# DRV8301.net
KiCad netlist of a schematic drawn in Altium Designer
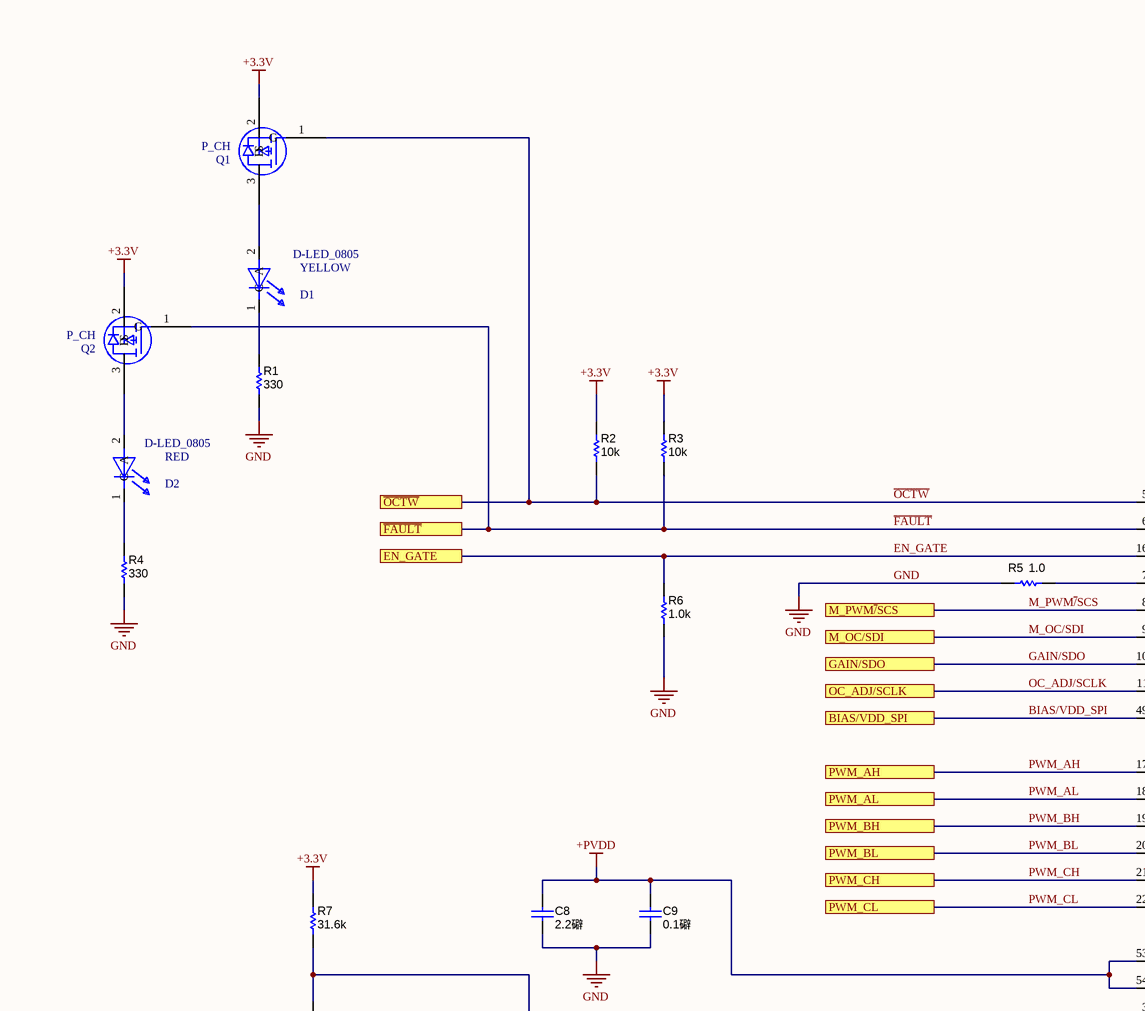
[diagram p0: DRV8301.SchDoc, top left]
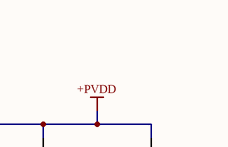
[diagram p1: DRV8301.SchDoc, top right]
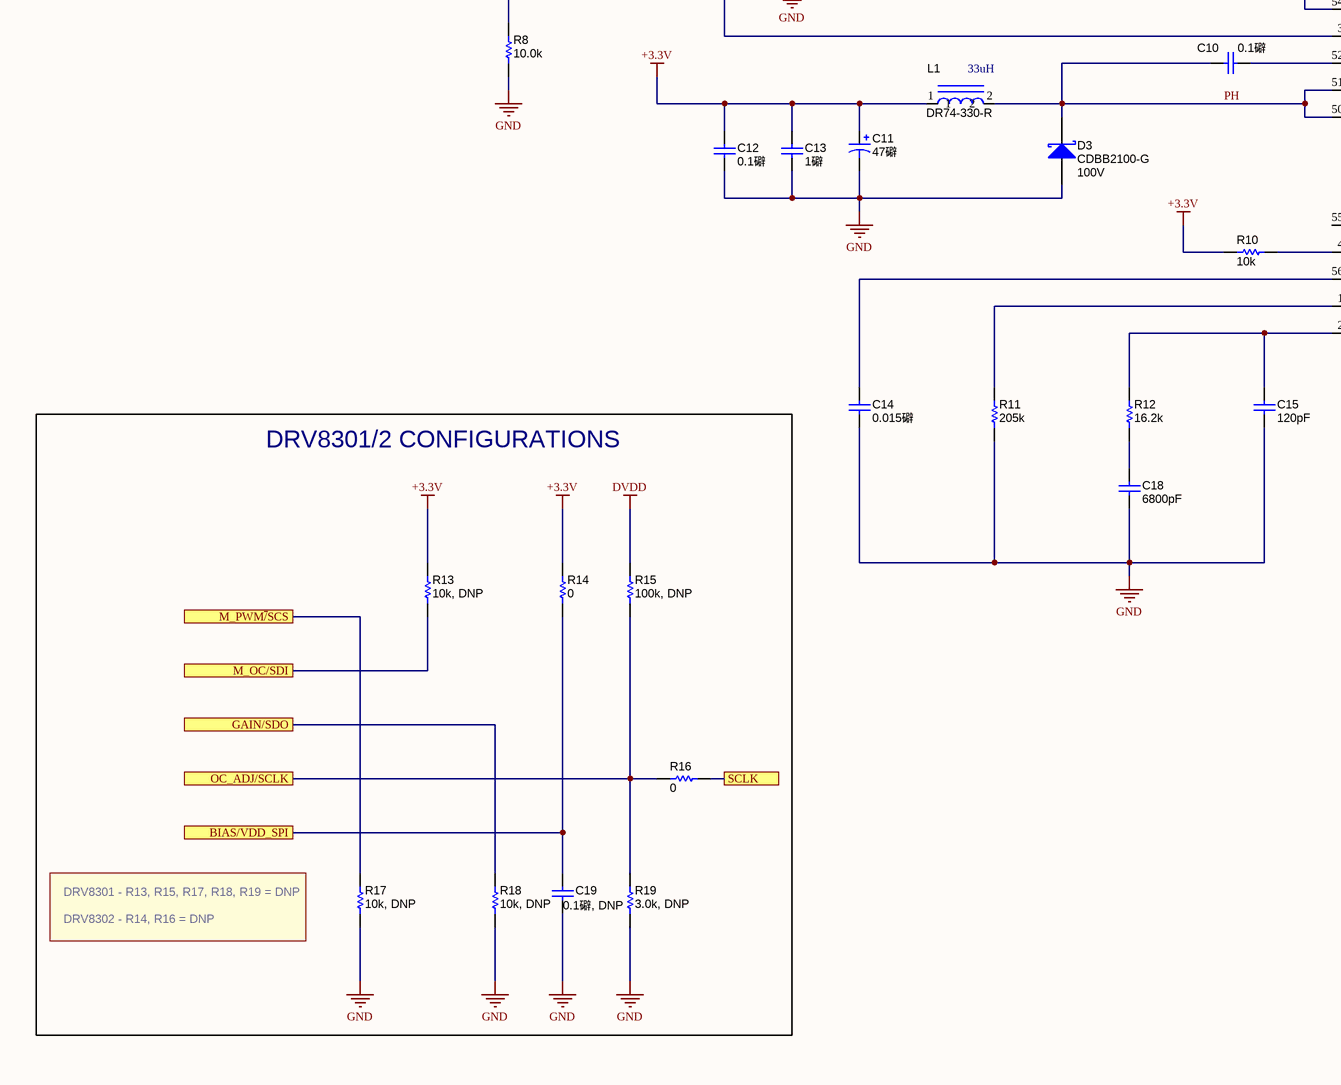
[diagram p2: DRV8301.SchDoc, bottom left]
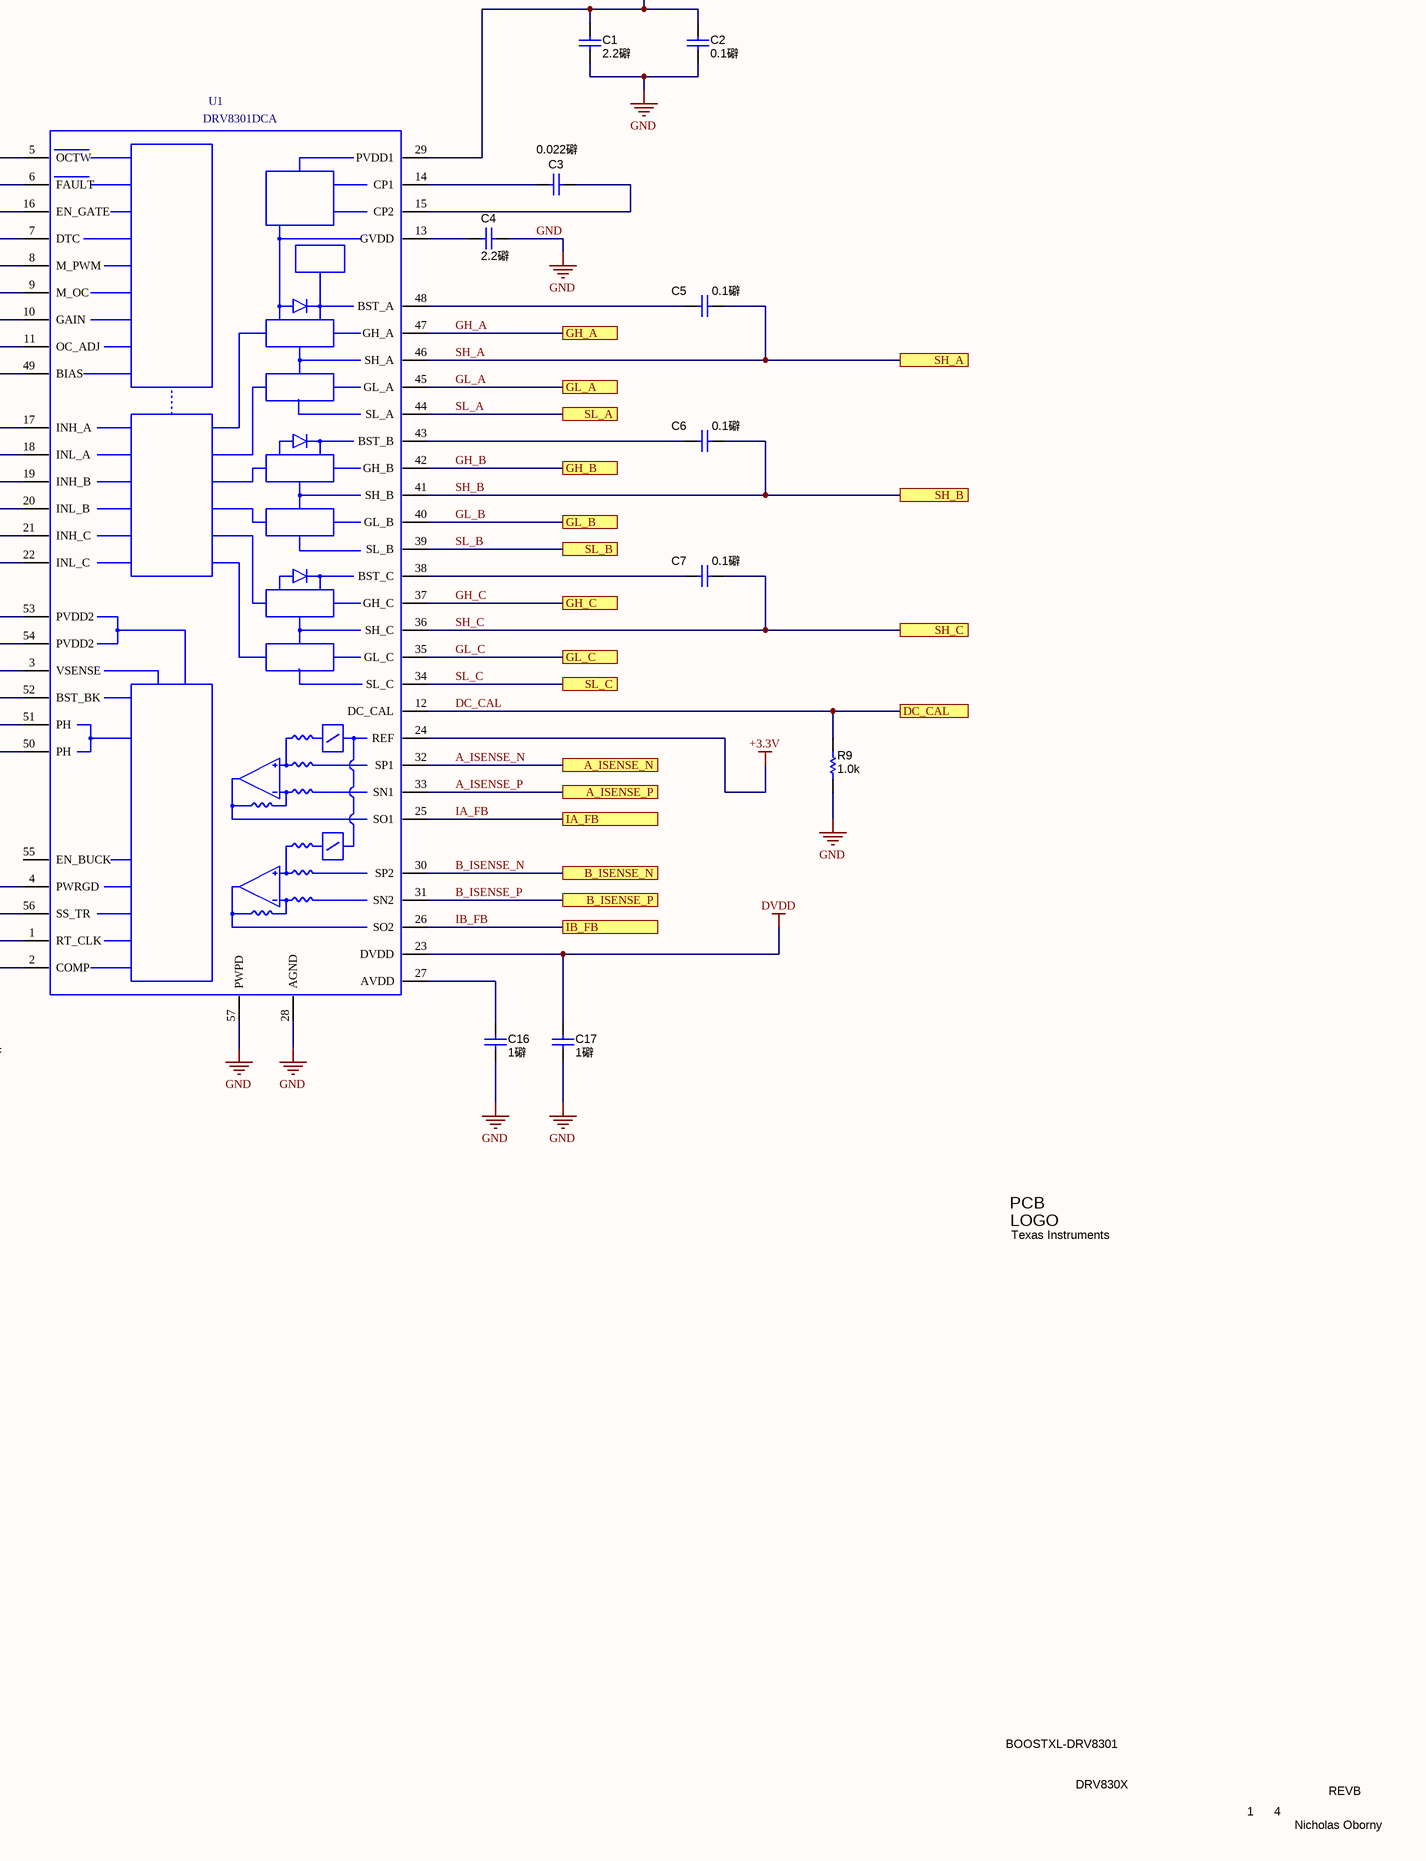
[diagram p3: DRV8301.SchDoc, bottom right]

(export (version "E")
  (design (tool "Eeschema 10.0.6"))
  (components
    (comp (ref "C1")
      (value "GRM32ER72A225KA35L")
      (footprint "1210L")
      (description "CAP, CERM, 2.2uF, 100V, +/-10%, X7R, 1210")
      (fields
        (field (name "VALUEDISPLAYED") "2.2礔")
        (field (name "MANUFACTURER") "MuRata")
        (field (name "PUBLISHER") "Texas Instruments")
      )
      (libsource (lib "Capacitor_Ceramic") (part "GRM32ER72A225KA35L"))
    )
    (comp (ref "C2")
      (value "GRM188R72A104KA35D")
      (footprint "0603L")
      (description "CAP, CERM, 0.1uF, 100V, +/-10%, X7R, 0603")
      (fields
        (field (name "VALUEDISPLAYED") "0.1礔")
        (field (name "MANUFACTURER") "MuRata")
        (field (name "PUBLISHER") "Texas Instruments")
      )
      (libsource (lib "Capacitor_Ceramic") (part "GRM188R72A104KA35D"))
    )
    (comp (ref "C3")
      (value "C1608X7R1H223K")
      (footprint "0603L")
      (description "CAP, CERM, 0.022uF, 50V, +/-10%, X7R, 0603")
      (fields
        (field (name "VALUEDISPLAYED") "0.022礔")
        (field (name "MANUFACTURER") "TDK")
        (field (name "PUBLISHER") "Texas Instruments")
      )
      (libsource (lib "Capacitor_Ceramic") (part "C1608X7R1H223K"))
    )
    (comp (ref "C4")
      (value "GRM219R61E225KA12D")
      (footprint "0805L")
      (description "CAP, CERM, 2.2uF, 25V, +/-10%, X5R, 0805")
      (fields
        (field (name "VALUEDISPLAYED") "2.2礔")
        (field (name "MANUFACTURER") "MuRata")
        (field (name "PUBLISHER") "Texas Instruments")
      )
      (libsource (lib "Capacitor_Ceramic") (part "GRM219R61E225KA12D"))
    )
    (comp (ref "C5")
      (value "C1608X7R1H104K")
      (footprint "0603L")
      (description "CAP, CERM, 0.1uF, 50V, +/-10%, X7R, 0603")
      (fields
        (field (name "VALUEDISPLAYED") "0.1礔")
        (field (name "MANUFACTURER") "TDK")
        (field (name "PUBLISHER") "Texas Instruments")
      )
      (libsource (lib "Capacitor_Ceramic") (part "C1608X7R1H104K"))
    )
    (comp (ref "C6")
      (value "C1608X7R1H104K")
      (footprint "0603L")
      (description "CAP, CERM, 0.1uF, 50V, +/-10%, X7R, 0603")
      (fields
        (field (name "VALUEDISPLAYED") "0.1礔")
        (field (name "MANUFACTURER") "TDK")
        (field (name "PUBLISHER") "Texas Instruments")
      )
      (libsource (lib "Capacitor_Ceramic") (part "C1608X7R1H104K"))
    )
    (comp (ref "C7")
      (value "C1608X7R1H104K")
      (footprint "0603L")
      (description "CAP, CERM, 0.1uF, 50V, +/-10%, X7R, 0603")
      (fields
        (field (name "VALUEDISPLAYED") "0.1礔")
        (field (name "MANUFACTURER") "TDK")
        (field (name "PUBLISHER") "Texas Instruments")
      )
      (libsource (lib "Capacitor_Ceramic") (part "C1608X7R1H104K"))
    )
    (comp (ref "C8")
      (value "GRM32ER72A225KA35L")
      (footprint "1210L")
      (description "CAP, CERM, 2.2uF, 100V, +/-10%, X7R, 1210")
      (fields
        (field (name "VALUEDISPLAYED") "2.2礔")
        (field (name "MANUFACTURER") "MuRata")
        (field (name "PUBLISHER") "Texas Instruments")
      )
      (libsource (lib "Capacitor_Ceramic") (part "GRM32ER72A225KA35L"))
    )
    (comp (ref "C9")
      (value "GRM188R72A104KA35D")
      (footprint "0603L")
      (description "CAP, CERM, 0.1uF, 100V, +/-10%, X7R, 0603")
      (fields
        (field (name "VALUEDISPLAYED") "0.1礔")
        (field (name "MANUFACTURER") "MuRata")
        (field (name "PUBLISHER") "Texas Instruments")
      )
      (libsource (lib "Capacitor_Ceramic") (part "GRM188R72A104KA35D"))
    )
    (comp (ref "C10")
      (value "C1608X7R1H104K")
      (footprint "0603L")
      (description "CAP, CERM, 0.1uF, 50V, +/-10%, X7R, 0603")
      (fields
        (field (name "VALUEDISPLAYED") "0.1礔")
        (field (name "MANUFACTURER") "TDK")
        (field (name "PUBLISHER") "Texas Instruments")
      )
      (libsource (lib "Capacitor_Ceramic") (part "C1608X7R1H104K"))
    )
    (comp (ref "C11")
      (value "EEE-FK1E470P")
      (footprint "SM_RADIAL_D")
      (description "CAP, AL, 47uF, 25V, +/-20%, 0.36 ohm, SMD")
      (fields
        (field (name "VALUEDISPLAYED") "47礔")
        (field (name "MANUFACTURER") "Panasonic")
        (field (name "PUBLISHER") "Texas Instruments")
      )
      (libsource (lib "Capacitor_Aluminum") (part "EEE-FK1E470P"))
    )
    (comp (ref "C12")
      (value "C1608X7R1E104K")
      (footprint "0603L")
      (description "CAP, CERM, 0.1uF, 25V, +/-10%, X7R, 0603")
      (fields
        (field (name "VALUEDISPLAYED") "0.1礔")
        (field (name "MANUFACTURER") "TDK")
        (field (name "PUBLISHER") "Texas Instruments")
      )
      (libsource (lib "Capacitor_Ceramic") (part "C1608X7R1E104K"))
    )
    (comp (ref "C13")
      (value "C1608X5R1E105K080AC")
      (footprint "0603L")
      (description "CAP, CERM, 1uF, 25V, +/-10%, X5R, 0603")
      (fields
        (field (name "VALUEDISPLAYED") "1礔")
        (field (name "MANUFACTURER") "TDK")
        (field (name "PUBLISHER") "Texas Instruments")
      )
      (libsource (lib "Capacitor_Ceramic") (part "C1608X5R1E105K080AC"))
    )
    (comp (ref "C14")
      (value "GRM188R71H153KA01D")
      (footprint "0603L")
      (description "CAP, CERM, 0.015uF, 50V, +/-10%, X7R, 0603")
      (fields
        (field (name "VALUEDISPLAYED") "0.015礔")
        (field (name "MANUFACTURER") "MuRata")
        (field (name "PUBLISHER") "Texas Instruments")
      )
      (libsource (lib "Capacitor_Ceramic") (part "GRM188R71H153KA01D"))
    )
    (comp (ref "C15")
      (value "GRM1885C1H121JA01D")
      (footprint "0603L")
      (description "CAP, CERM, 120pF, 50V, +/-5%, C0G/NP0, 0603")
      (fields
        (field (name "VALUEDISPLAYED") "120pF")
        (field (name "MANUFACTURER") "MuRata")
        (field (name "PUBLISHER") "Texas Instruments")
      )
      (libsource (lib "Capacitor_Ceramic") (part "GRM1885C1H121JA01D"))
    )
    (comp (ref "C16")
      (value "GRM188R61E105KA12D")
      (footprint "0603L")
      (description "CAP, CERM, 1uF, 25V, +/-10%, X5R, 0603")
      (fields
        (field (name "VALUEDISPLAYED") "1礔")
        (field (name "MANUFACTURER") "MuRata")
        (field (name "PUBLISHER") "Texas Instruments")
      )
      (libsource (lib "Capacitor_Ceramic") (part "GRM188R61E105KA12D"))
    )
    (comp (ref "C17")
      (value "GRM188R61E105KA12D")
      (footprint "0603L")
      (description "CAP, CERM, 1uF, 25V, +/-10%, X5R, 0603")
      (fields
        (field (name "VALUEDISPLAYED") "1礔")
        (field (name "MANUFACTURER") "MuRata")
        (field (name "PUBLISHER") "Texas Instruments")
      )
      (libsource (lib "Capacitor_Ceramic") (part "GRM188R61E105KA12D"))
    )
    (comp (ref "C18")
      (value "GRM188R71H682KA01D")
      (footprint "0603L")
      (description "CAP, CERM, 6800pF, 50V, +/-10%, X7R, 0603")
      (fields
        (field (name "VALUEDISPLAYED") "6800pF")
        (field (name "MANUFACTURER") "MuRata")
        (field (name "PUBLISHER") "Texas Instruments")
      )
      (libsource (lib "Capacitor_Ceramic") (part "GRM188R71H682KA01D"))
    )
    (comp (ref "C19")
      (value "C1608X7R1E104K")
      (footprint "0603L")
      (description "CAP, CERM, 0.1uF, 25V, +/-10%, X7R, 0603")
      (fields
        (field (name "VALUEDISPLAYED") "0.1礔, DNP")
        (field (name "MANUFACTURER") "TDK")
        (field (name "PUBLISHER") "Texas Instruments")
      )
      (libsource (lib "Capacitor_Ceramic") (part "C1608X7R1E104K"))
    )
    (comp (ref "D1")
      (value "D-LED_0805")
      (footprint "LED_0805")
      (description "LED THIN 585NM YEL DIFF 0805 SMD")
      (fields
        (field (name "PARTNUMBER") "SML-LXT0805YW-TR")
        (field (name "ALTIUM_VALUE") "YELLOW")
        (field (name "MANUFACTURER") "Lumex Opto/Components Inc")
      )
      (libsource (lib "*") (part "D-LED_0805"))
    )
    (comp (ref "D2")
      (value "D-LED_0805")
      (footprint "LED_0805")
      (description "LED THIN660NM SUPRED DIFF0805SMD")
      (fields
        (field (name "PARTNUMBER") "SML-LXT0805SRW-TR")
        (field (name "ALTIUM_VALUE") "RED")
        (field (name "MANUFACTURER") "Lumex Opto/Components Inc")
      )
      (libsource (lib "*") (part "D-LED_0805"))
    )
    (comp (ref "D3")
      (value "CDBB2100-G")
      (footprint "SMB")
      (description "Diode, Schottky, 100V, 2A, SMB")
      (fields
        (field (name "ALTIUM_VALUE") "100V")
        (field (name "MANUFACTURER") "Comchip Technology")
        (field (name "PUBLISHER") "Texas Instruments")
      )
      (libsource (lib "Diode") (part "CDBC5100-G"))
    )
    (comp (ref "L1")
      (value "DR74-330-R")
      (footprint "IND_DR74")
      (description "INDUCTOR SHIELD PWR 33UH SMD")
      (fields (field (name "MANUFACTURER") "Cooper Bussmann") (field (name "ALTIUM_VALUE") "33uH"))
      (libsource (lib "PADSlegacy_Passive") (part "IND_DR74-XXX"))
    )
    (comp (ref "Logo1")
      (value "Texas Instruments")
      (footprint "TI_Symbol_Overlay_Small")
      (description "Texas Instrument Corporate Signature")
      (fields (field (name "SYMBOLCREATOR") "codlsc") (field (name "PUBLISHER") "Texas Instruments"))
      (libsource (lib "Logos") (part "TI_Logo"))
    )
    (comp (ref "Q1")
      (value "P_CH")
      (footprint "SOT-23")
      (description "MOSFET P-CH 8V 5.4A SOT23-3")
      (fields (field (name "PARTNUMBER") "SI2325DS-T1-E3") (field (name "MANUFACTURER") "Vishey Siliconix"))
      (libsource (lib "*") (part "TR_PFET_SOT23"))
    )
    (comp (ref "Q2")
      (value "P_CH")
      (footprint "SOT-23")
      (description "MOSFET P-CH 8V 5.4A SOT23-3")
      (fields (field (name "PARTNUMBER") "SI2325DS-T1-E3") (field (name "MANUFACTURER") "Vishey Siliconix"))
      (libsource (lib "*") (part "TR_PFET_SOT23"))
    )
    (comp (ref "R1")
      (value "330")
      (footprint "0603L")
      (description "RES, 330 ohm, 5%, 0.1W, 0603")
      (fields
        (field (name "PARTNUMBER") "CRCW0603330RJNEA")
        (field (name "MANUFACTURER") "Vishay-Dale")
        (field (name "PUBLISHER") "Texas Instruments")
      )
      (libsource (lib "Resistor_0603") (part "CRCW0603330RJNEA"))
    )
    (comp (ref "R2")
      (value "10k")
      (footprint "0603L")
      (description "RES, 10k ohm, 5%, 0.1W, 0603")
      (fields
        (field (name "PARTNUMBER") "CRCW060310K0JNEA")
        (field (name "MANUFACTURER") "Vishay-Dale")
        (field (name "PUBLISHER") "Texas Instruments")
      )
      (libsource (lib "Resistor_0603") (part "CRCW060310K0JNEA"))
    )
    (comp (ref "R3")
      (value "10k")
      (footprint "0603L")
      (description "RES, 10k ohm, 5%, 0.1W, 0603")
      (fields
        (field (name "PARTNUMBER") "CRCW060310K0JNEA")
        (field (name "MANUFACTURER") "Vishay-Dale")
        (field (name "PUBLISHER") "Texas Instruments")
      )
      (libsource (lib "Resistor_0603") (part "CRCW060310K0JNEA"))
    )
    (comp (ref "R4")
      (value "330")
      (footprint "0603L")
      (description "RES, 330 ohm, 5%, 0.1W, 0603")
      (fields
        (field (name "PARTNUMBER") "CRCW0603330RJNEA")
        (field (name "MANUFACTURER") "Vishay-Dale")
        (field (name "PUBLISHER") "Texas Instruments")
      )
      (libsource (lib "Resistor_0603") (part "CRCW0603330RJNEA"))
    )
    (comp (ref "R5")
      (value "1.0")
      (footprint "0603L")
      (description "RES, 1.0 ohm, 5%, 0.1W, 0603")
      (fields
        (field (name "PARTNUMBER") "CRCW06031R00JNEA")
        (field (name "MANUFACTURER") "Vishay-Dale")
        (field (name "PUBLISHER") "Texas Instruments")
      )
      (libsource (lib "Resistor_0603") (part "CRCW06031R00JNEA"))
    )
    (comp (ref "R6")
      (value "1.0k")
      (footprint "0603L")
      (description "RES, 1.0k ohm, 5%, 0.1W, 0603")
      (fields
        (field (name "PARTNUMBER") "CRCW06031K00JNEA")
        (field (name "MANUFACTURER") "Vishay-Dale")
        (field (name "PUBLISHER") "Texas Instruments")
      )
      (libsource (lib "Resistor_0603") (part "CRCW06031K00JNEA"))
    )
    (comp (ref "R7")
      (value "31.6k")
      (footprint "0603L")
      (description "RES, 31.6k ohm, 1%, 0.1W, 0603")
      (fields
        (field (name "PARTNUMBER") "CRCW060331K6FKEA")
        (field (name "MANUFACTURER") "Vishay-Dale")
        (field (name "PUBLISHER") "Texas Instruments")
      )
      (libsource (lib "Resistor_0603") (part "CRCW060331K6FKEA"))
    )
    (comp (ref "R8")
      (value "10.0k")
      (footprint "0603L")
      (description "RES, 10.0k ohm, 0.1%, 0.1W, 0603")
      (fields
        (field (name "PARTNUMBER") "RG1608P-103-B-T5")
        (field (name "MANUFACTURER") "Susumu Co Ltd")
        (field (name "PUBLISHER") "Texas Instruments")
      )
      (libsource (lib "Resistor_0603") (part "RG1608P-103-B-T5"))
    )
    (comp (ref "R9")
      (value "1.0k")
      (footprint "0603L")
      (description "RES, 1.0k ohm, 5%, 0.1W, 0603")
      (fields
        (field (name "PARTNUMBER") "CRCW06031K00JNEA")
        (field (name "MANUFACTURER") "Vishay-Dale")
        (field (name "PUBLISHER") "Texas Instruments")
      )
      (libsource (lib "Resistor_0603") (part "CRCW06031K00JNEA"))
    )
    (comp (ref "R10")
      (value "10k")
      (footprint "0603L")
      (description "RES, 10k ohm, 5%, 0.1W, 0603")
      (fields
        (field (name "PARTNUMBER") "CRCW060310K0JNEA")
        (field (name "MANUFACTURER") "Vishay-Dale")
        (field (name "PUBLISHER") "Texas Instruments")
      )
      (libsource (lib "Resistor_0603") (part "CRCW060310K0JNEA"))
    )
    (comp (ref "R11")
      (value "205k")
      (footprint "0603L")
      (description "RES, 205k ohm, 1%, 0.1W, 0603")
      (fields
        (field (name "PARTNUMBER") "CRCW0603205KFKEA")
        (field (name "MANUFACTURER") "Vishay-Dale")
        (field (name "PUBLISHER") "Texas Instruments")
      )
      (libsource (lib "Resistor_0603") (part "CRCW0603205KFKEA"))
    )
    (comp (ref "R12")
      (value "16.2k")
      (footprint "0603L")
      (description "RES, 16.2k ohm, 1%, 0.1W, 0603")
      (fields
        (field (name "PARTNUMBER") "CRCW060316K2FKEA")
        (field (name "MANUFACTURER") "Vishay-Dale")
        (field (name "PUBLISHER") "Texas Instruments")
      )
      (libsource (lib "Resistor_0603") (part "CRCW060316K2FKEA"))
    )
    (comp (ref "R13")
      (value "10k, DNP")
      (footprint "0603L")
      (description "RES, 10k ohm, 5%, 0.1W, 0603")
      (fields
        (field (name "PARTNUMBER") "CRCW060310K0JNEA")
        (field (name "MANUFACTURER") "Vishay-Dale")
        (field (name "PUBLISHER") "Texas Instruments")
      )
      (libsource (lib "Resistor_0603") (part "CRCW060310K0JNEA"))
    )
    (comp (ref "R14")
      (value "0")
      (footprint "0603L")
      (description "RES, 0 ohm, 5%, 0.1W, 0603")
      (fields
        (field (name "PARTNUMBER") "CRCW06030000Z0EA")
        (field (name "MANUFACTURER") "Vishay-Dale")
        (field (name "PUBLISHER") "Texas Instruments")
      )
      (libsource (lib "Resistor_0603") (part "CRCW06030000Z0EA"))
    )
    (comp (ref "R15")
      (value "100k, DNP")
      (footprint "0603L")
      (description "RES, 100k ohm, 5%, 0.1W, 0603")
      (fields
        (field (name "PARTNUMBER") "CRCW0603100KJNEA")
        (field (name "MANUFACTURER") "Vishay-Dale")
        (field (name "PUBLISHER") "Texas Instruments")
      )
      (libsource (lib "Resistor_0603") (part "CRCW0603100KJNEA"))
    )
    (comp (ref "R16")
      (value "0")
      (footprint "0603L")
      (description "RES, 0 ohm, 5%, 0.1W, 0603")
      (fields
        (field (name "PARTNUMBER") "CRCW06030000Z0EA")
        (field (name "MANUFACTURER") "Vishay-Dale")
        (field (name "PUBLISHER") "Texas Instruments")
      )
      (libsource (lib "Resistor_0603") (part "CRCW06030000Z0EA"))
    )
    (comp (ref "R17")
      (value "10k, DNP")
      (footprint "0603L")
      (description "RES, 10k ohm, 5%, 0.1W, 0603")
      (fields
        (field (name "PARTNUMBER") "CRCW060310K0JNEA")
        (field (name "MANUFACTURER") "Vishay-Dale")
        (field (name "PUBLISHER") "Texas Instruments")
      )
      (libsource (lib "Resistor_0603") (part "CRCW060310K0JNEA"))
    )
    (comp (ref "R18")
      (value "10k, DNP")
      (footprint "0603L")
      (description "RES, 10k ohm, 5%, 0.1W, 0603")
      (fields
        (field (name "PARTNUMBER") "CRCW060310K0JNEA")
        (field (name "MANUFACTURER") "Vishay-Dale")
        (field (name "PUBLISHER") "Texas Instruments")
      )
      (libsource (lib "Resistor_0603") (part "CRCW060310K0JNEA"))
    )
    (comp (ref "R19")
      (value "3.0k, DNP")
      (footprint "0603L")
      (description "RES, 3.0k ohm, 5%, 0.1W, 0603")
      (fields
        (field (name "PARTNUMBER") "CRCW06033K00JNEA")
        (field (name "MANUFACTURER") "Vishay-Dale")
        (field (name "PUBLISHER") "Texas Instruments")
      )
      (libsource (lib "Resistor_0603") (part "CRCW06033K00JNEA"))
    )
    (comp (ref "U1")
      (value "DRV8301DCA")
      (footprint "DCA_56P")
      (description "IC, 3 Phase Pre-Driver with Dual Current Shunt Amplifiers and Buck Regulator-Hardware Controlled")
      (fields (field (name "MANUFACTURER") "Texas Instruments") (field (name "VENDOR PART #") "Supplied"))
      (libsource (lib "*") (part "DRV8302DCA_ERIC"))
    )
  )
  (nets
    (net (code "1") (name "+3.3V") (class "Default")
      (node (ref "C11") (pin "1") (pinfunction "+_1") (pintype "passive"))
      (node (ref "C12") (pin "1") (pinfunction "1_1") (pintype "passive"))
      (node (ref "C13") (pin "1") (pinfunction "1_1") (pintype "passive"))
      (node (ref "L1") (pin "1") (pinfunction "1_1") (pintype "passive"))
      (node (ref "Q1") (pin "2") (pinfunction "S_2") (pintype "passive"))
      (node (ref "Q2") (pin "2") (pinfunction "S_2") (pintype "passive"))
      (node (ref "R10") (pin "2") (pinfunction "2_2") (pintype "passive"))
      (node (ref "R13") (pin "2") (pinfunction "2_2") (pintype "passive"))
      (node (ref "R14") (pin "2") (pinfunction "2_2") (pintype "passive"))
      (node (ref "R2") (pin "2") (pinfunction "2_2") (pintype "passive"))
      (node (ref "R3") (pin "2") (pinfunction "2_2") (pintype "passive"))
      (node (ref "R7") (pin "2") (pinfunction "2_2") (pintype "passive"))
      (node (ref "U1") (pin "24") (pinfunction "REF_24") (pintype "passive"))
    )
    (net (code "2") (name "+PVDD") (class "Default")
      (node (ref "C1") (pin "1") (pinfunction "1_1") (pintype "passive"))
      (node (ref "C2") (pin "1") (pinfunction "1_1") (pintype "passive"))
      (node (ref "C8") (pin "1") (pinfunction "1_1") (pintype "passive"))
      (node (ref "C9") (pin "1") (pinfunction "1_1") (pintype "passive"))
      (node (ref "U1") (pin "29") (pinfunction "PVDD1_29") (pintype "passive"))
      (node (ref "U1") (pin "53") (pinfunction "PVDD2_53") (pintype "passive"))
      (node (ref "U1") (pin "54") (pinfunction "PVDD2_54") (pintype "passive"))
    )
    (net (code "3") (name "/A_ISENSE_N") (class "Default")
      (node (ref "U1") (pin "32") (pinfunction "SP1_32") (pintype "passive"))
    )
    (net (code "4") (name "/A_ISENSE_P") (class "Default")
      (node (ref "U1") (pin "33") (pinfunction "SN1_33") (pintype "passive"))
    )
    (net (code "5") (name "/BIAS{slash}VDD_SPI") (class "Default")
      (node (ref "C19") (pin "1") (pinfunction "1_1") (pintype "passive"))
      (node (ref "R14") (pin "1") (pinfunction "1_1") (pintype "passive"))
      (node (ref "U1") (pin "49") (pinfunction "BIAS_49") (pintype "passive"))
    )
    (net (code "6") (name "/B_ISENSE_N") (class "Default")
      (node (ref "U1") (pin "30") (pinfunction "SP2_30") (pintype "passive"))
    )
    (net (code "7") (name "/B_ISENSE_P") (class "Default")
      (node (ref "U1") (pin "31") (pinfunction "SN2_31") (pintype "passive"))
    )
    (net (code "8") (name "/DC_CAL") (class "Default")
      (node (ref "R9") (pin "2") (pinfunction "2_2") (pintype "passive"))
      (node (ref "U1") (pin "12") (pinfunction "DC_CAL_12") (pintype "passive"))
    )
    (net (code "9") (name "/EN_GATE") (class "Default")
      (node (ref "R6") (pin "2") (pinfunction "2_2") (pintype "passive"))
      (node (ref "U1") (pin "16") (pinfunction "EN_GATE_16") (pintype "passive"))
    )
    (net (code "10") (name "/FAULT") (class "Default")
      (node (ref "Q2") (pin "1") (pinfunction "G_1") (pintype "passive"))
      (node (ref "R3") (pin "1") (pinfunction "1_1") (pintype "passive"))
      (node (ref "U1") (pin "6") (pinfunction "FAULT_6") (pintype "passive"))
    )
    (net (code "11") (name "/GAIN{slash}SDO") (class "Default")
      (node (ref "R18") (pin "2") (pinfunction "2_2") (pintype "passive"))
      (node (ref "U1") (pin "10") (pinfunction "GAIN_10") (pintype "passive"))
    )
    (net (code "12") (name "/GH_A") (class "Default")
      (node (ref "U1") (pin "47") (pinfunction "GH_A_47") (pintype "passive"))
    )
    (net (code "13") (name "/GH_B") (class "Default")
      (node (ref "U1") (pin "42") (pinfunction "GH_B_42") (pintype "passive"))
    )
    (net (code "14") (name "/GH_C") (class "Default")
      (node (ref "U1") (pin "37") (pinfunction "GH_C_37") (pintype "passive"))
    )
    (net (code "15") (name "/GL_A") (class "Default")
      (node (ref "U1") (pin "45") (pinfunction "GL_A_45") (pintype "passive"))
    )
    (net (code "16") (name "/GL_B") (class "Default")
      (node (ref "U1") (pin "40") (pinfunction "GL_B_40") (pintype "passive"))
    )
    (net (code "17") (name "/GL_C") (class "Default")
      (node (ref "U1") (pin "35") (pinfunction "GL_C_35") (pintype "passive"))
    )
    (net (code "18") (name "/IA_FB") (class "Default")
      (node (ref "U1") (pin "25") (pinfunction "SO1_25") (pintype "passive"))
    )
    (net (code "19") (name "/IB_FB") (class "Default")
      (node (ref "U1") (pin "26") (pinfunction "SO2_26") (pintype "passive"))
    )
    (net (code "20") (name "/M_OC{slash}SDI") (class "Default")
      (node (ref "R13") (pin "1") (pinfunction "1_1") (pintype "passive"))
      (node (ref "U1") (pin "9") (pinfunction "M_OC_9") (pintype "passive"))
    )
    (net (code "21") (name "/M_PWM~{{slash}}SCS") (class "Default")
      (node (ref "R17") (pin "2") (pinfunction "2_2") (pintype "passive"))
      (node (ref "U1") (pin "8") (pinfunction "M_PWM_8") (pintype "passive"))
    )
    (net (code "22") (name "/OCTW") (class "Default")
      (node (ref "Q1") (pin "1") (pinfunction "G_1") (pintype "passive"))
      (node (ref "R2") (pin "1") (pinfunction "1_1") (pintype "passive"))
      (node (ref "U1") (pin "5") (pinfunction "OCTW_5") (pintype "passive"))
    )
    (net (code "23") (name "/OC_ADJ{slash}SCLK") (class "Default")
      (node (ref "R15") (pin "2") (pinfunction "2_2") (pintype "passive"))
      (node (ref "R16") (pin "2") (pinfunction "2_2") (pintype "passive"))
      (node (ref "R19") (pin "2") (pinfunction "2_2") (pintype "passive"))
      (node (ref "U1") (pin "11") (pinfunction "OC_ADJ_11") (pintype "passive"))
    )
    (net (code "24") (name "/PH") (class "Default")
      (node (ref "C10") (pin "1") (pinfunction "1_1") (pintype "passive"))
      (node (ref "D3") (pin "1") (pinfunction "K_1") (pintype "passive"))
      (node (ref "L1") (pin "2") (pinfunction "2_2") (pintype "passive"))
      (node (ref "U1") (pin "50") (pinfunction "PH_50") (pintype "passive"))
      (node (ref "U1") (pin "51") (pinfunction "PH_51") (pintype "passive"))
    )
    (net (code "25") (name "/PWM_AH") (class "Default")
      (node (ref "U1") (pin "17") (pinfunction "INH_A_17") (pintype "passive"))
    )
    (net (code "26") (name "/PWM_AL") (class "Default")
      (node (ref "U1") (pin "18") (pinfunction "INL_A_18") (pintype "passive"))
    )
    (net (code "27") (name "/PWM_BH") (class "Default")
      (node (ref "U1") (pin "19") (pinfunction "INH_B_19") (pintype "passive"))
    )
    (net (code "28") (name "/PWM_BL") (class "Default")
      (node (ref "U1") (pin "20") (pinfunction "INL_B_20") (pintype "passive"))
    )
    (net (code "29") (name "/PWM_CH") (class "Default")
      (node (ref "U1") (pin "21") (pinfunction "INH_C_21") (pintype "passive"))
    )
    (net (code "30") (name "/PWM_CL") (class "Default")
      (node (ref "U1") (pin "22") (pinfunction "INL_C_22") (pintype "passive"))
    )
    (net (code "31") (name "/SCLK") (class "Default")
      (node (ref "R16") (pin "1") (pinfunction "1_1") (pintype "passive"))
    )
    (net (code "32") (name "/SH_A") (class "Default")
      (node (ref "C5") (pin "2") (pinfunction "2_2") (pintype "passive"))
      (node (ref "U1") (pin "46") (pinfunction "SH_A_46") (pintype "passive"))
    )
    (net (code "33") (name "/SH_B") (class "Default")
      (node (ref "C6") (pin "2") (pinfunction "2_2") (pintype "passive"))
      (node (ref "U1") (pin "41") (pinfunction "SH_B_41") (pintype "passive"))
    )
    (net (code "34") (name "/SH_C") (class "Default")
      (node (ref "C7") (pin "2") (pinfunction "2_2") (pintype "passive"))
      (node (ref "U1") (pin "36") (pinfunction "SH_C_36") (pintype "passive"))
    )
    (net (code "35") (name "/SL_A") (class "Default")
      (node (ref "U1") (pin "44") (pinfunction "SL_A_44") (pintype "passive"))
    )
    (net (code "36") (name "/SL_B") (class "Default")
      (node (ref "U1") (pin "39") (pinfunction "SL_B_39") (pintype "passive"))
    )
    (net (code "37") (name "/SL_C") (class "Default")
      (node (ref "U1") (pin "34") (pinfunction "SL_C_34") (pintype "passive"))
    )
    (net (code "38") (name "DVDD") (class "Default")
      (node (ref "C17") (pin "1") (pinfunction "1_1") (pintype "passive"))
      (node (ref "R15") (pin "1") (pinfunction "1_1") (pintype "passive"))
      (node (ref "U1") (pin "23") (pinfunction "DVDD_23") (pintype "passive"))
    )
    (net (code "39") (name "GND") (class "Default")
      (node (ref "C1") (pin "2") (pinfunction "2_2") (pintype "passive"))
      (node (ref "C11") (pin "2") (pinfunction "-_2") (pintype "passive"))
      (node (ref "C12") (pin "2") (pinfunction "2_2") (pintype "passive"))
      (node (ref "C13") (pin "2") (pinfunction "2_2") (pintype "passive"))
      (node (ref "C14") (pin "2") (pinfunction "2_2") (pintype "passive"))
      (node (ref "C15") (pin "2") (pinfunction "2_2") (pintype "passive"))
      (node (ref "C16") (pin "2") (pinfunction "2_2") (pintype "passive"))
      (node (ref "C17") (pin "2") (pinfunction "2_2") (pintype "passive"))
      (node (ref "C18") (pin "2") (pinfunction "2_2") (pintype "passive"))
      (node (ref "C19") (pin "2") (pinfunction "2_2") (pintype "passive"))
      (node (ref "C2") (pin "2") (pinfunction "2_2") (pintype "passive"))
      (node (ref "C4") (pin "2") (pinfunction "2_2") (pintype "passive"))
      (node (ref "C8") (pin "2") (pinfunction "2_2") (pintype "passive"))
      (node (ref "C9") (pin "2") (pinfunction "2_2") (pintype "passive"))
      (node (ref "D3") (pin "2") (pinfunction "A_2") (pintype "passive"))
      (node (ref "R1") (pin "1") (pinfunction "1_1") (pintype "passive"))
      (node (ref "R11") (pin "1") (pinfunction "1_1") (pintype "passive"))
      (node (ref "R17") (pin "1") (pinfunction "1_1") (pintype "passive"))
      (node (ref "R18") (pin "1") (pinfunction "1_1") (pintype "passive"))
      (node (ref "R19") (pin "1") (pinfunction "1_1") (pintype "passive"))
      (node (ref "R4") (pin "1") (pinfunction "1_1") (pintype "passive"))
      (node (ref "R5") (pin "1") (pinfunction "1_1") (pintype "passive"))
      (node (ref "R6") (pin "1") (pinfunction "1_1") (pintype "passive"))
      (node (ref "R8") (pin "1") (pinfunction "1_1") (pintype "passive"))
      (node (ref "R9") (pin "1") (pinfunction "1_1") (pintype "passive"))
      (node (ref "U1") (pin "28") (pinfunction "AGND_28") (pintype "passive"))
      (node (ref "U1") (pin "57") (pinfunction "PWPD_57") (pintype "passive"))
    )
    (net (code "40") (name "Net-(C18-Pad1)") (class "Default")
      (node (ref "C18") (pin "1") (pinfunction "1_1") (pintype "passive"))
      (node (ref "R12") (pin "1") (pinfunction "1_1") (pintype "passive"))
    )
    (net (code "41") (name "Net-(D1-A)") (class "Default")
      (node (ref "D1") (pin "2") (pinfunction "A_2") (pintype "passive"))
      (node (ref "Q1") (pin "3") (pinfunction "D_3") (pintype "passive"))
    )
    (net (code "42") (name "Net-(D1-C)") (class "Default")
      (node (ref "D1") (pin "1") (pinfunction "C_1") (pintype "passive"))
      (node (ref "R1") (pin "2") (pinfunction "2_2") (pintype "passive"))
    )
    (net (code "43") (name "Net-(D2-A)") (class "Default")
      (node (ref "D2") (pin "2") (pinfunction "A_2") (pintype "passive"))
      (node (ref "Q2") (pin "3") (pinfunction "D_3") (pintype "passive"))
    )
    (net (code "44") (name "Net-(D2-C)") (class "Default")
      (node (ref "D2") (pin "1") (pinfunction "C_1") (pintype "passive"))
      (node (ref "R4") (pin "2") (pinfunction "2_2") (pintype "passive"))
    )
    (net (code "45") (name "Net-(U1-AVDD)") (class "Default")
      (node (ref "C16") (pin "1") (pinfunction "1_1") (pintype "passive"))
      (node (ref "U1") (pin "27") (pinfunction "AVDD_27") (pintype "passive"))
    )
    (net (code "46") (name "Net-(U1-BST_A)") (class "Default")
      (node (ref "C5") (pin "1") (pinfunction "1_1") (pintype "passive"))
      (node (ref "U1") (pin "48") (pinfunction "BST_A_48") (pintype "passive"))
    )
    (net (code "47") (name "Net-(U1-BST_B)") (class "Default")
      (node (ref "C6") (pin "1") (pinfunction "1_1") (pintype "passive"))
      (node (ref "U1") (pin "43") (pinfunction "BST_B_43") (pintype "passive"))
    )
    (net (code "48") (name "Net-(U1-BST_BK)") (class "Default")
      (node (ref "C10") (pin "2") (pinfunction "2_2") (pintype "passive"))
      (node (ref "U1") (pin "52") (pinfunction "BST_BK_52") (pintype "passive"))
    )
    (net (code "49") (name "Net-(U1-BST_C)") (class "Default")
      (node (ref "C7") (pin "1") (pinfunction "1_1") (pintype "passive"))
      (node (ref "U1") (pin "38") (pinfunction "BST_C_38") (pintype "passive"))
    )
    (net (code "50") (name "Net-(U1-COMP)") (class "Default")
      (node (ref "C15") (pin "1") (pinfunction "1_1") (pintype "passive"))
      (node (ref "R12") (pin "2") (pinfunction "2_2") (pintype "passive"))
      (node (ref "U1") (pin "2") (pinfunction "COMP_2") (pintype "passive"))
    )
    (net (code "51") (name "Net-(U1-CP1)") (class "Default")
      (node (ref "C3") (pin "1") (pinfunction "1_1") (pintype "passive"))
      (node (ref "U1") (pin "14") (pinfunction "CP1_14") (pintype "passive"))
    )
    (net (code "52") (name "Net-(U1-CP2)") (class "Default")
      (node (ref "C3") (pin "2") (pinfunction "2_2") (pintype "passive"))
      (node (ref "U1") (pin "15") (pinfunction "CP2_15") (pintype "passive"))
    )
    (net (code "53") (name "Net-(U1-DTC)") (class "Default")
      (node (ref "R5") (pin "2") (pinfunction "2_2") (pintype "passive"))
      (node (ref "U1") (pin "7") (pinfunction "DTC_7") (pintype "passive"))
    )
    (net (code "54") (name "Net-(U1-GVDD)") (class "Default")
      (node (ref "C4") (pin "1") (pinfunction "1_1") (pintype "passive"))
      (node (ref "U1") (pin "13") (pinfunction "GVDD_13") (pintype "passive"))
    )
    (net (code "55") (name "Net-(U1-PWRGD)") (class "Default")
      (node (ref "R10") (pin "1") (pinfunction "1_1") (pintype "passive"))
      (node (ref "U1") (pin "4") (pinfunction "PWRGD_4") (pintype "passive"))
    )
    (net (code "56") (name "Net-(U1-RT_CLK)") (class "Default")
      (node (ref "R11") (pin "2") (pinfunction "2_2") (pintype "passive"))
      (node (ref "U1") (pin "1") (pinfunction "RT_CLK_1") (pintype "passive"))
    )
    (net (code "57") (name "Net-(U1-SS_TR)") (class "Default")
      (node (ref "C14") (pin "1") (pinfunction "1_1") (pintype "passive"))
      (node (ref "U1") (pin "56") (pinfunction "SS_TR_56") (pintype "passive"))
    )
    (net (code "58") (name "Net-(U1-VSENSE)") (class "Default")
      (node (ref "R7") (pin "1") (pinfunction "1_1") (pintype "passive"))
      (node (ref "R8") (pin "2") (pinfunction "2_2") (pintype "passive"))
      (node (ref "U1") (pin "3") (pinfunction "VSENSE_3") (pintype "passive"))
    )
    (net (code "59") (name "unconnected-(U1-EN_BUCK-Pad55)") (class "Default")
      (node (ref "U1") (pin "55") (pinfunction "EN_BUCK_55") (pintype "passive"))
    )
  )
)
